# OSIVE_Slim_DUE-Shield.net
KiCad netlist of a schematic drawn in EAGLE
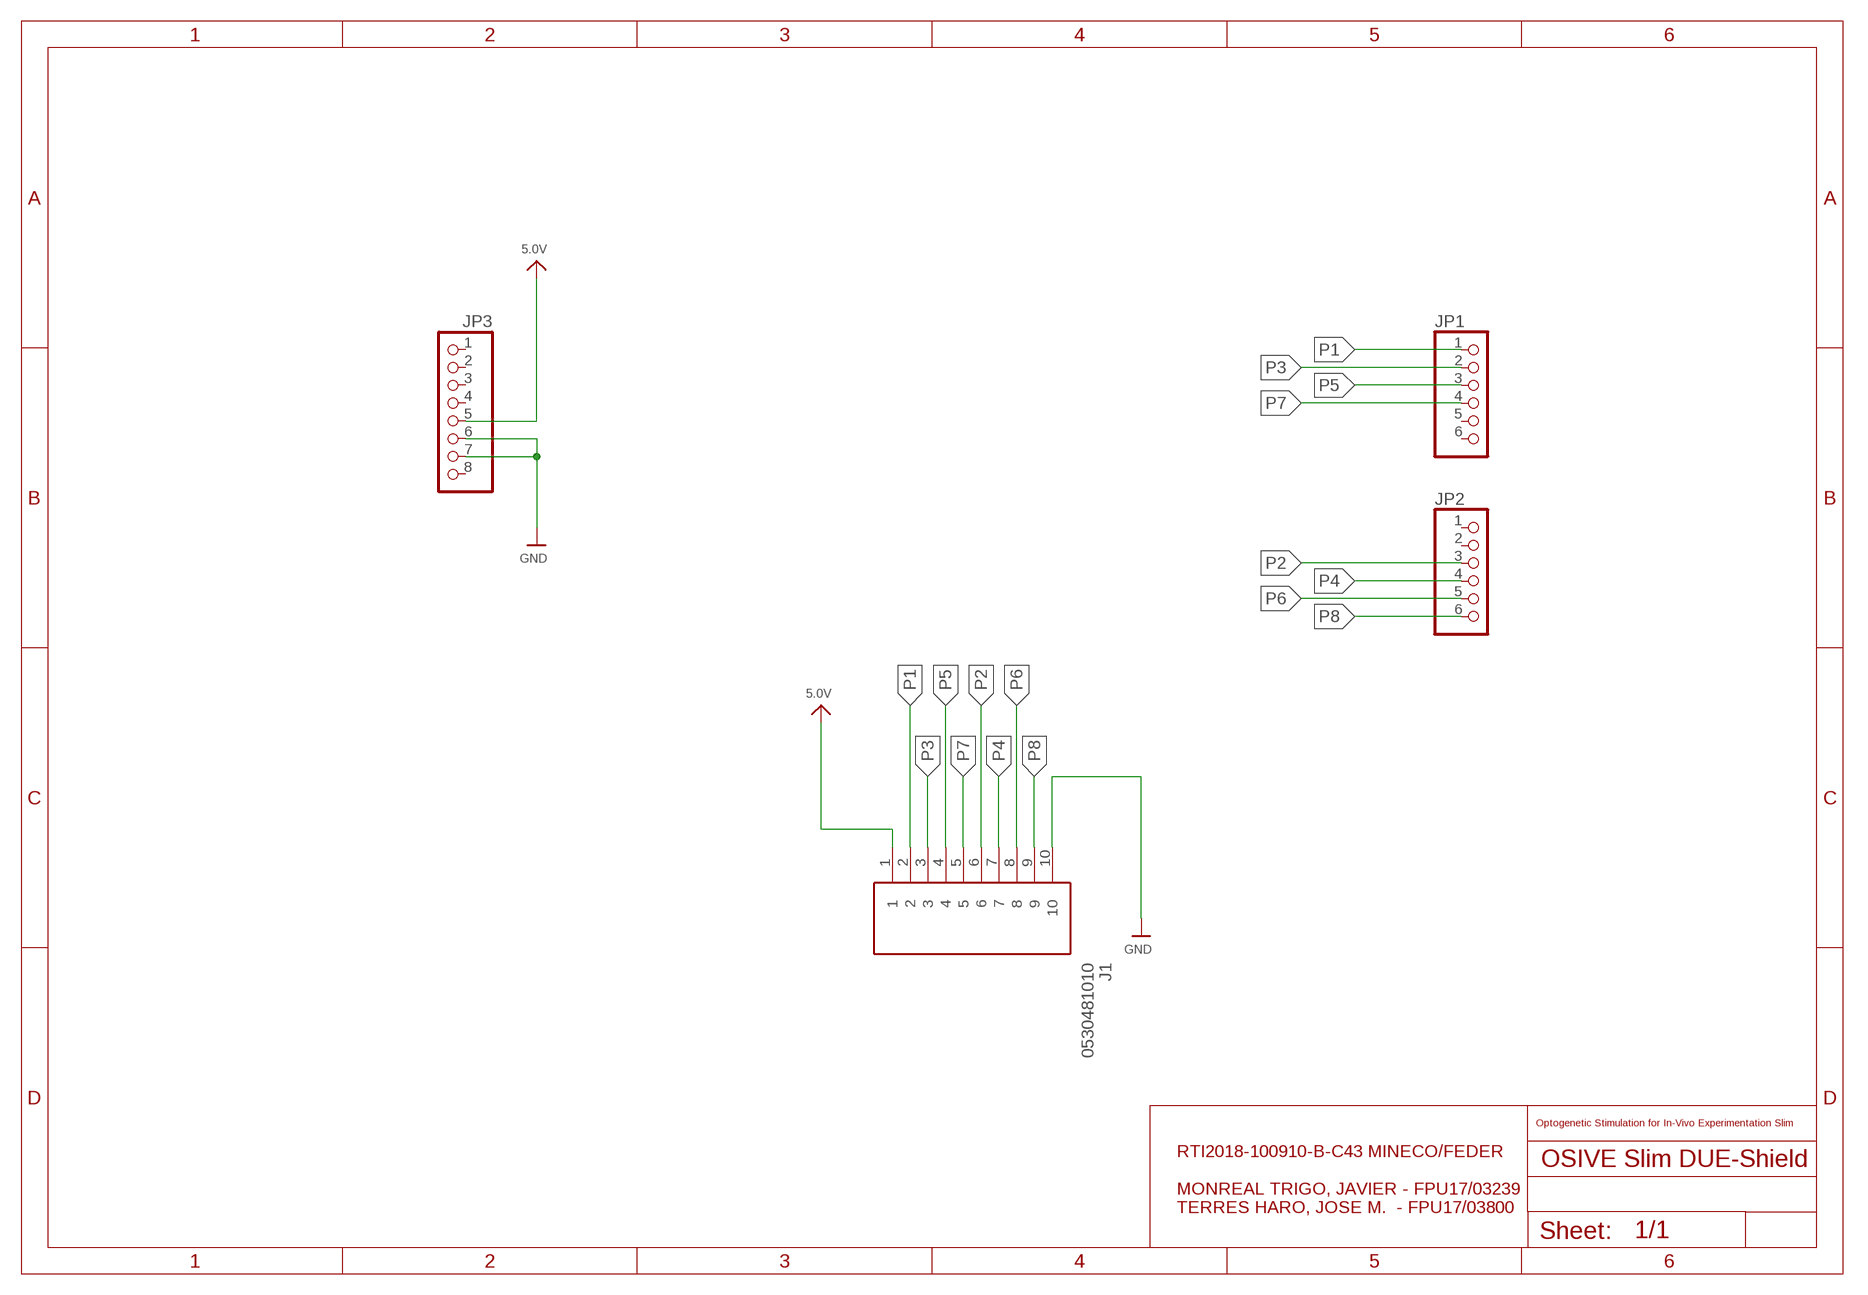
[diagram p0: schematic, sheet 1]

(export (version "E")
  (design (tool "Eeschema 10.0.6"))
  (components
    (comp (ref "J1")
      (value "0530481010")
      (footprint "eagle-import:0530481010")
      (libsource (lib "eagle-import") (part "0530481010"))
    )
    (comp (ref "JP1")
      (value "HEADER-1X6")
      (footprint "eagle-import:1X06_OVAL")
      (libsource (lib "eagle-import") (part "HEADER-1X6"))
    )
    (comp (ref "JP2")
      (value "HEADER-1X6")
      (footprint "eagle-import:1X06_OVAL")
      (libsource (lib "eagle-import") (part "HEADER-1X6"))
    )
    (comp (ref "JP3")
      (value "HEADER-1X8")
      (footprint "eagle-import:1X08_OVAL")
      (libsource (lib "eagle-import") (part "HEADER-1X8"))
    )
  )
  (nets
    (net (code "1") (name "5.0V") (class "Default")
      (node (ref "J1") (pin "1") (pinfunction "1_1") (pintype "bidirectional"))
      (node (ref "JP3") (pin "5") (pinfunction "5_5") (pintype "passive"))
    )
    (net (code "2") (name "GND") (class "Default")
      (node (ref "J1") (pin "10") (pinfunction "10_10") (pintype "bidirectional"))
      (node (ref "JP3") (pin "6") (pinfunction "6_6") (pintype "passive"))
      (node (ref "JP3") (pin "7") (pinfunction "7_7") (pintype "passive"))
    )
    (net (code "3") (name "P1") (class "Default")
      (node (ref "J1") (pin "2") (pinfunction "2_2") (pintype "bidirectional"))
      (node (ref "JP1") (pin "1") (pinfunction "1_1") (pintype "passive"))
    )
    (net (code "4") (name "P2") (class "Default")
      (node (ref "J1") (pin "6") (pinfunction "6_6") (pintype "bidirectional"))
      (node (ref "JP2") (pin "3") (pinfunction "3_3") (pintype "passive"))
    )
    (net (code "5") (name "P3") (class "Default")
      (node (ref "J1") (pin "3") (pinfunction "3_3") (pintype "bidirectional"))
      (node (ref "JP1") (pin "2") (pinfunction "2_2") (pintype "passive"))
    )
    (net (code "6") (name "P4") (class "Default")
      (node (ref "J1") (pin "7") (pinfunction "7_7") (pintype "bidirectional"))
      (node (ref "JP2") (pin "4") (pinfunction "4_4") (pintype "passive"))
    )
    (net (code "7") (name "P5") (class "Default")
      (node (ref "J1") (pin "4") (pinfunction "4_4") (pintype "bidirectional"))
      (node (ref "JP1") (pin "3") (pinfunction "3_3") (pintype "passive"))
    )
    (net (code "8") (name "P6") (class "Default")
      (node (ref "J1") (pin "8") (pinfunction "8_8") (pintype "bidirectional"))
      (node (ref "JP2") (pin "5") (pinfunction "5_5") (pintype "passive"))
    )
    (net (code "9") (name "P7") (class "Default")
      (node (ref "J1") (pin "5") (pinfunction "5_5") (pintype "bidirectional"))
      (node (ref "JP1") (pin "4") (pinfunction "4_4") (pintype "passive"))
    )
    (net (code "10") (name "P8") (class "Default")
      (node (ref "J1") (pin "9") (pinfunction "9_9") (pintype "bidirectional"))
      (node (ref "JP2") (pin "6") (pinfunction "6_6") (pintype "passive"))
    )
    (net (code "11") (name "unconnected-(JP1-Pad5)") (class "Default")
      (node (ref "JP1") (pin "5") (pinfunction "5_5") (pintype "passive"))
    )
    (net (code "12") (name "unconnected-(JP1-Pad6)") (class "Default")
      (node (ref "JP1") (pin "6") (pinfunction "6_6") (pintype "passive"))
    )
    (net (code "13") (name "unconnected-(JP2-Pad1)") (class "Default")
      (node (ref "JP2") (pin "1") (pinfunction "1_1") (pintype "passive"))
    )
    (net (code "14") (name "unconnected-(JP2-Pad2)") (class "Default")
      (node (ref "JP2") (pin "2") (pinfunction "2_2") (pintype "passive"))
    )
    (net (code "15") (name "unconnected-(JP3-Pad1)") (class "Default")
      (node (ref "JP3") (pin "1") (pinfunction "1_1") (pintype "passive"))
    )
    (net (code "16") (name "unconnected-(JP3-Pad2)") (class "Default")
      (node (ref "JP3") (pin "2") (pinfunction "2_2") (pintype "passive"))
    )
    (net (code "17") (name "unconnected-(JP3-Pad3)") (class "Default")
      (node (ref "JP3") (pin "3") (pinfunction "3_3") (pintype "passive"))
    )
    (net (code "18") (name "unconnected-(JP3-Pad4)") (class "Default")
      (node (ref "JP3") (pin "4") (pinfunction "4_4") (pintype "passive"))
    )
    (net (code "19") (name "unconnected-(JP3-Pad8)") (class "Default")
      (node (ref "JP3") (pin "8") (pinfunction "8_8") (pintype "passive"))
    )
  )
)
